# 5250_converter.net
KiCad netlist of a schematic drawn in EAGLE
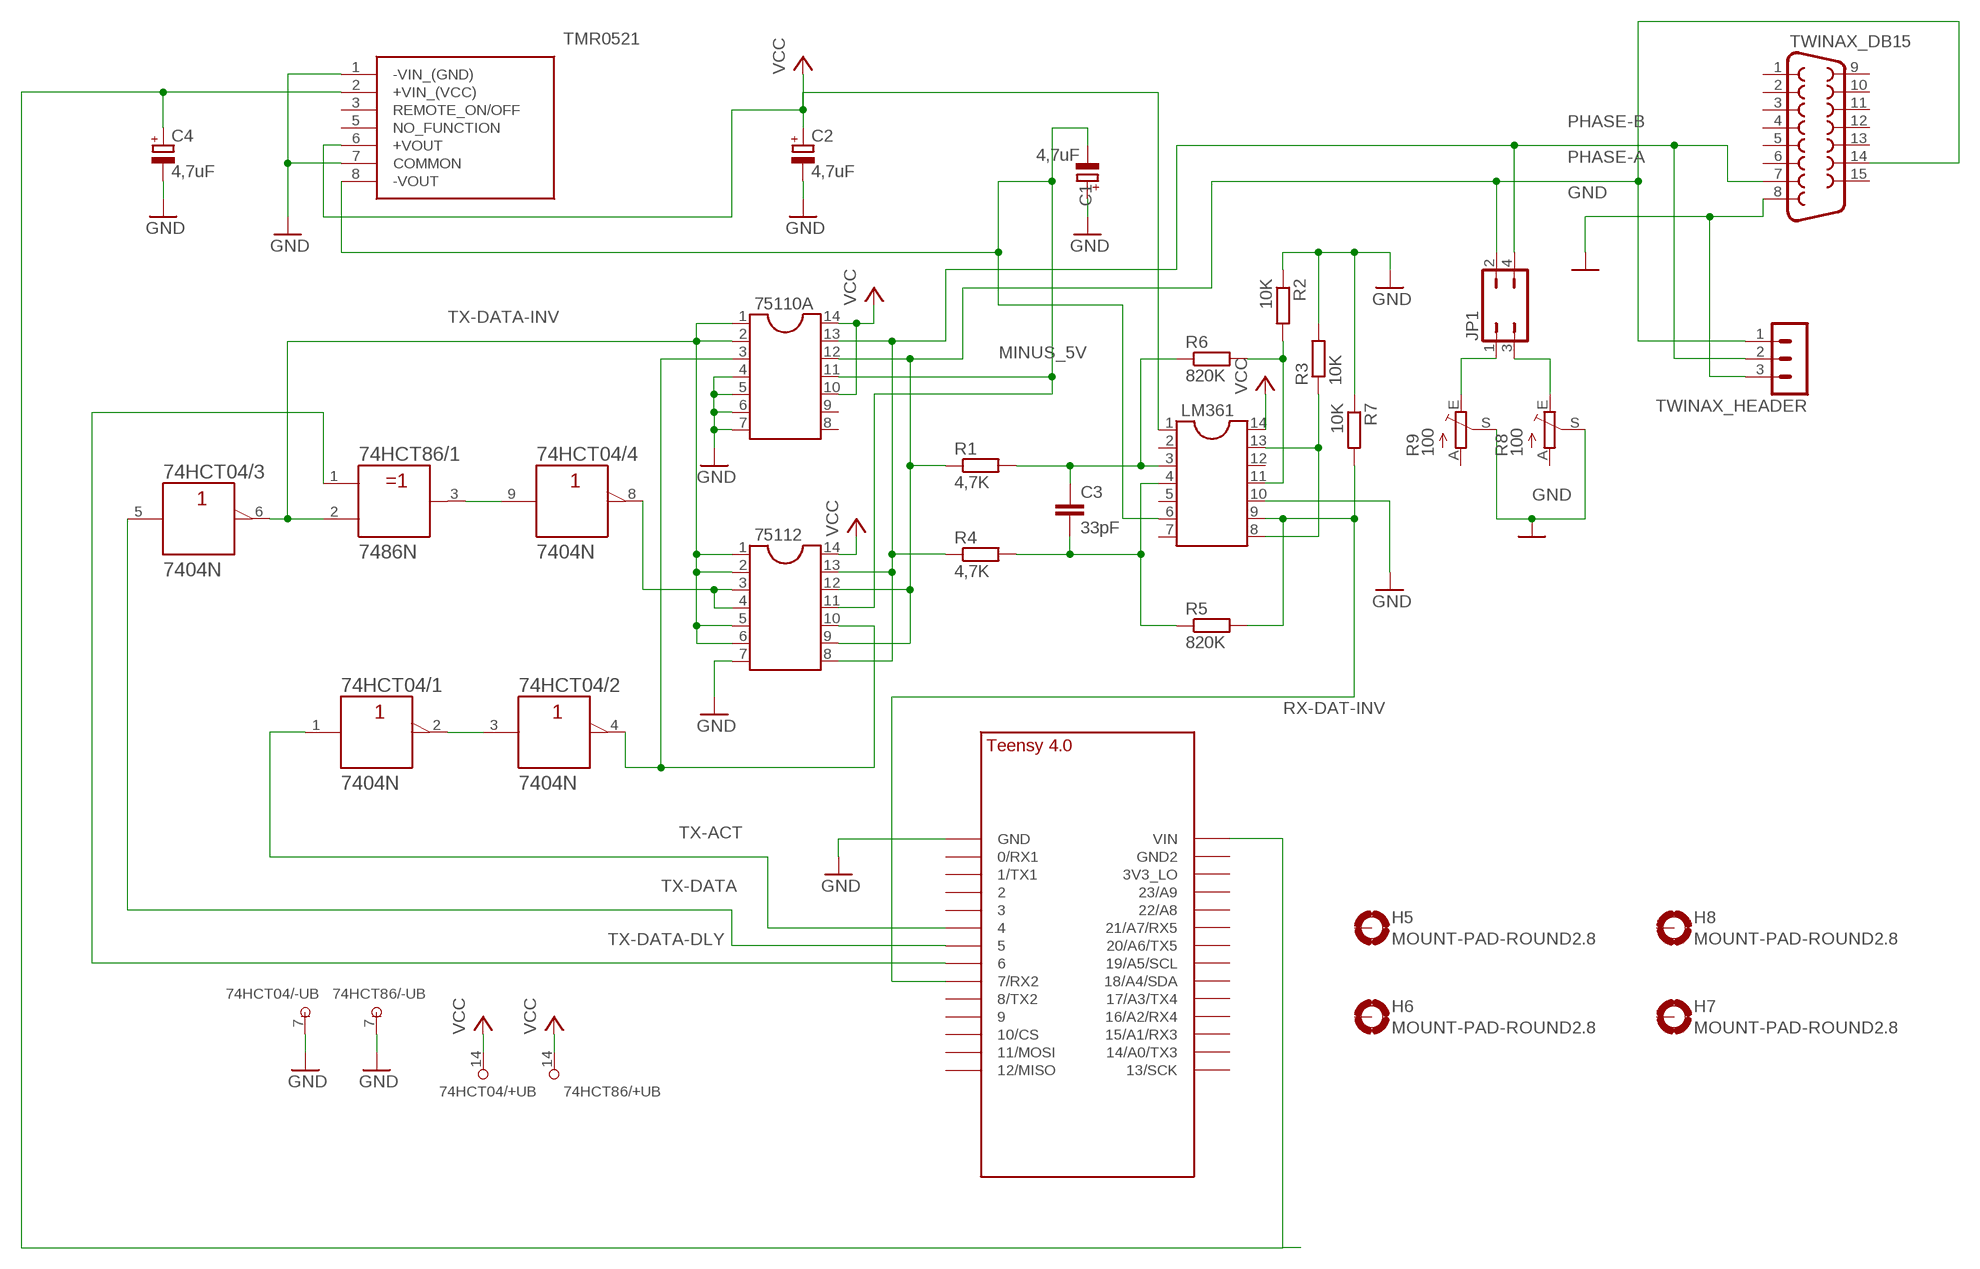
[diagram p0: schematic, sheet 1]

(export (version "E")
  (design (tool "Eeschema 10.0.6"))
  (components
    (comp (ref "74HCT04")
      (value "7404N")
      (footprint "eagle-import:DIL14")
      (libsource (lib "eagle-import") (part "7404N"))
    )
    (comp (ref "74HCT86")
      (value "7486N")
      (footprint "eagle-import:DIL14")
      (libsource (lib "eagle-import") (part "7486N"))
    )
    (comp (ref "75110A")
      (value "DIL14")
      (footprint "eagle-import:DIL14")
      (libsource (lib "eagle-import") (part "DIL14"))
    )
    (comp (ref "75112")
      (value "DIL14")
      (footprint "eagle-import:DIL14")
      (libsource (lib "eagle-import") (part "DIL14"))
    )
    (comp (ref "C1")
      (value "4,7uF")
      (footprint "eagle-import:E2,5-6")
      (libsource (lib "eagle-import") (part "CPOL-EUE2.5-6"))
    )
    (comp (ref "C2")
      (value "4,7uF")
      (footprint "eagle-import:E2,5-6")
      (libsource (lib "eagle-import") (part "CPOL-EUE2.5-6"))
    )
    (comp (ref "C3")
      (value "33pF")
      (footprint "eagle-import:C050-030X075")
      (libsource (lib "eagle-import") (part "C-EU050-030X075"))
    )
    (comp (ref "C4")
      (value "4,7uF")
      (footprint "eagle-import:E2,5-6")
      (libsource (lib "eagle-import") (part "CPOL-EUE2.5-6"))
    )
    (comp (ref "H5")
      (value "MOUNT-PAD-ROUND2.8")
      (footprint "eagle-import:2,8-PAD")
      (libsource (lib "eagle-import") (part "MOUNT-PAD-ROUND2.8"))
    )
    (comp (ref "H6")
      (value "MOUNT-PAD-ROUND2.8")
      (footprint "eagle-import:2,8-PAD")
      (libsource (lib "eagle-import") (part "MOUNT-PAD-ROUND2.8"))
    )
    (comp (ref "H7")
      (value "MOUNT-PAD-ROUND2.8")
      (footprint "eagle-import:2,8-PAD")
      (libsource (lib "eagle-import") (part "MOUNT-PAD-ROUND2.8"))
    )
    (comp (ref "H8")
      (value "MOUNT-PAD-ROUND2.8")
      (footprint "eagle-import:2,8-PAD")
      (libsource (lib "eagle-import") (part "MOUNT-PAD-ROUND2.8"))
    )
    (comp (ref "JP1")
      (value "JP2Q")
      (footprint "eagle-import:JP2Q")
      (libsource (lib "eagle-import") (part "JP2Q"))
    )
    (comp (ref "LM361")
      (value "DIL14")
      (footprint "eagle-import:DIL14")
      (libsource (lib "eagle-import") (part "DIL14"))
    )
    (comp (ref "R1")
      (value "4,7K")
      (footprint "eagle-import:0207_10")
      (libsource (lib "eagle-import") (part "R-EU_0207/10"))
    )
    (comp (ref "R2")
      (value "10K")
      (footprint "eagle-import:0207_10")
      (libsource (lib "eagle-import") (part "R-EU_0207/10"))
    )
    (comp (ref "R3")
      (value "10K")
      (footprint "eagle-import:0207_10")
      (libsource (lib "eagle-import") (part "R-EU_0207/10"))
    )
    (comp (ref "R4")
      (value "4,7K")
      (footprint "eagle-import:0207_10")
      (libsource (lib "eagle-import") (part "R-EU_0207/10"))
    )
    (comp (ref "R5")
      (value "820K")
      (footprint "eagle-import:0207_10")
      (libsource (lib "eagle-import") (part "R-EU_0207/10"))
    )
    (comp (ref "R6")
      (value "820K")
      (footprint "eagle-import:0207_10")
      (libsource (lib "eagle-import") (part "R-EU_0207/10"))
    )
    (comp (ref "R7")
      (value "10K")
      (footprint "eagle-import:0207_10")
      (libsource (lib "eagle-import") (part "R-EU_0207/10"))
    )
    (comp (ref "R8")
      (value "100")
      (footprint "eagle-import:CA9V")
      (libsource (lib "eagle-import") (part "TRIM_EU-CA9V"))
    )
    (comp (ref "R9")
      (value "100")
      (footprint "eagle-import:CA9V")
      (libsource (lib "eagle-import") (part "TRIM_EU-CA9V"))
    )
    (comp (ref "TMR0521")
      (value "TMR0521")
      (footprint "eagle-import:TMR0521")
      (fields
        (field (name "MANUFACTURER_PART_NUMBER") "TMR 3-2422")
        (field (name "MOUSER_PART_NUMBER") "495-TMR-3-2422")
        (field (name "RS_PART_NUMBER") "0438082")
      )
      (libsource (lib "eagle-import") (part "TMR0521TMR0521"))
    )
    (comp (ref "TWINAX_DB15")
      (value "F15H")
      (footprint "eagle-import:F15H")
      (libsource (lib "eagle-import") (part "F15H"))
    )
    (comp (ref "TWINAX_HEADER")
      (value "MA03-1")
      (footprint "eagle-import:MA03-1")
      (libsource (lib "eagle-import") (part "MA03-1"))
    )
    (comp (ref "U$1")
      (value "TEENSY_4.0-BASIC")
      (footprint "eagle-import:TEENSY_4.0-BASIC")
      (libsource (lib "eagle-import") (part "TEENSY_4.0-BASIC"))
    )
  )
  (nets
    (net (code "1") (name "/MINUS_5V") (class "Default")
      (node (ref "75110A") (pin "11") (pinfunction "11_11") (pintype "passive"))
      (node (ref "75112") (pin "11") (pinfunction "11_11") (pintype "passive"))
      (node (ref "C1") (pin "-") (pinfunction "-_-") (pintype "passive"))
      (node (ref "LM361") (pin "6") (pinfunction "6_6") (pintype "passive"))
      (node (ref "TMR0521") (pin "8") (pinfunction "-VOUT_8") (pintype "bidirectional"))
    )
    (net (code "2") (name "/PHASE-A") (class "Default")
      (node (ref "75110A") (pin "12") (pinfunction "12_12") (pintype "passive"))
      (node (ref "75112") (pin "12") (pinfunction "12_12") (pintype "passive"))
      (node (ref "75112") (pin "9") (pinfunction "9_9") (pintype "passive"))
      (node (ref "JP1") (pin "2") (pinfunction "2_2") (pintype "passive"))
      (node (ref "R1") (pin "1") (pinfunction "1_1") (pintype "passive"))
      (node (ref "TWINAX_DB15") (pin "14") (pinfunction "14_14") (pintype "passive"))
      (node (ref "TWINAX_HEADER") (pin "1") (pinfunction "1_1") (pintype "passive"))
    )
    (net (code "3") (name "/PHASE-B") (class "Default")
      (node (ref "75110A") (pin "13") (pinfunction "13_13") (pintype "passive"))
      (node (ref "75112") (pin "13") (pinfunction "13_13") (pintype "passive"))
      (node (ref "75112") (pin "8") (pinfunction "8_8") (pintype "passive"))
      (node (ref "JP1") (pin "4") (pinfunction "4_4") (pintype "passive"))
      (node (ref "R4") (pin "1") (pinfunction "1_1") (pintype "passive"))
      (node (ref "TWINAX_DB15") (pin "7") (pinfunction "7_7") (pintype "passive"))
      (node (ref "TWINAX_HEADER") (pin "2") (pinfunction "2_2") (pintype "passive"))
    )
    (net (code "4") (name "/RX-DAT-INV") (class "Default")
      (node (ref "LM361") (pin "9") (pinfunction "9_9") (pintype "passive"))
      (node (ref "R5") (pin "2") (pinfunction "2_2") (pintype "passive"))
      (node (ref "R7") (pin "2") (pinfunction "2_2") (pintype "passive"))
      (node (ref "U$1") (pin "7") (pinfunction "7/RX2_7") (pintype "bidirectional"))
    )
    (net (code "5") (name "/TX-ACT") (class "Default")
      (node (ref "74HCT04") (pin "1") (pinfunction "A_1") (pintype "input"))
      (node (ref "U$1") (pin "4/CANRX") (pinfunction "4_4/CANRX") (pintype "bidirectional"))
    )
    (net (code "6") (name "/TX-DATA") (class "Default")
      (node (ref "74HCT04") (pin "5") (pinfunction "A_5") (pintype "input"))
      (node (ref "U$1") (pin "5") (pinfunction "5_5") (pintype "bidirectional"))
    )
    (net (code "7") (name "/TX-DATA-DLY") (class "Default")
      (node (ref "74HCT86") (pin "1") (pinfunction "A_1") (pintype "input"))
      (node (ref "U$1") (pin "6") (pinfunction "6_6") (pintype "bidirectional"))
    )
    (net (code "8") (name "/TX-DATA-INV") (class "Default")
      (node (ref "74HCT04") (pin "6") (pinfunction "Y_6") (pintype "output"))
      (node (ref "74HCT86") (pin "2") (pinfunction "B_2") (pintype "input"))
      (node (ref "75110A") (pin "1") (pinfunction "1_1") (pintype "passive"))
      (node (ref "75110A") (pin "2") (pinfunction "2_2") (pintype "passive"))
      (node (ref "75112") (pin "1") (pinfunction "1_1") (pintype "passive"))
      (node (ref "75112") (pin "2") (pinfunction "2_2") (pintype "passive"))
      (node (ref "75112") (pin "5") (pinfunction "5_5") (pintype "passive"))
      (node (ref "75112") (pin "6") (pinfunction "6_6") (pintype "passive"))
    )
    (net (code "9") (name "GND") (class "Default")
      (node (ref "74HCT04") (pin "7") (pinfunction "-UB_7") (pintype "power_in"))
      (node (ref "74HCT86") (pin "7") (pinfunction "-UB_7") (pintype "power_in"))
      (node (ref "75110A") (pin "4") (pinfunction "4_4") (pintype "passive"))
      (node (ref "75110A") (pin "5") (pinfunction "5_5") (pintype "passive"))
      (node (ref "75110A") (pin "6") (pinfunction "6_6") (pintype "passive"))
      (node (ref "75110A") (pin "7") (pinfunction "7_7") (pintype "passive"))
      (node (ref "75112") (pin "7") (pinfunction "7_7") (pintype "passive"))
      (node (ref "C1") (pin "+") (pinfunction "+_+") (pintype "passive"))
      (node (ref "C2") (pin "-") (pinfunction "-_-") (pintype "passive"))
      (node (ref "C4") (pin "-") (pinfunction "-_-") (pintype "passive"))
      (node (ref "LM361") (pin "10") (pinfunction "10_10") (pintype "passive"))
      (node (ref "R2") (pin "1") (pinfunction "1_1") (pintype "passive"))
      (node (ref "R3") (pin "2") (pinfunction "2_2") (pintype "passive"))
      (node (ref "R7") (pin "1") (pinfunction "1_1") (pintype "passive"))
      (node (ref "R8") (pin "S") (pinfunction "S_S") (pintype "passive"))
      (node (ref "R9") (pin "S") (pinfunction "S_S") (pintype "passive"))
      (node (ref "TMR0521") (pin "1") (pinfunction "-VIN_(GND)_1") (pintype "bidirectional"))
      (node (ref "TMR0521") (pin "7") (pinfunction "COMMON_7") (pintype "bidirectional"))
      (node (ref "TWINAX_DB15") (pin "8") (pinfunction "8_8") (pintype "passive"))
      (node (ref "TWINAX_HEADER") (pin "3") (pinfunction "3_3") (pintype "passive"))
      (node (ref "U$1") (pin "GND") (pinfunction "GND_GND") (pintype "bidirectional"))
    )
    (net (code "10") (name "Net-(74HCT04C-Y)") (class "Default")
      (node (ref "74HCT04") (pin "2") (pinfunction "Y_2") (pintype "output"))
      (node (ref "74HCT04") (pin "3") (pinfunction "A_3") (pintype "input"))
    )
    (net (code "11") (name "Net-(74HCT04D-Y)") (class "Default")
      (node (ref "74HCT04") (pin "4") (pinfunction "Y_4") (pintype "output"))
      (node (ref "75110A") (pin "3") (pinfunction "3_3") (pintype "passive"))
      (node (ref "75112") (pin "10") (pinfunction "10_10") (pintype "passive"))
    )
    (net (code "12") (name "Net-(74HCT04F-A)") (class "Default")
      (node (ref "74HCT04") (pin "9") (pinfunction "A_9") (pintype "input"))
      (node (ref "74HCT86") (pin "3") (pinfunction "Y_3") (pintype "output"))
    )
    (net (code "13") (name "Net-(74HCT04F-Y)") (class "Default")
      (node (ref "74HCT04") (pin "8") (pinfunction "Y_8") (pintype "output"))
      (node (ref "75112") (pin "3") (pinfunction "3_3") (pintype "passive"))
      (node (ref "75112") (pin "4") (pinfunction "4_4") (pintype "passive"))
    )
    (net (code "14") (name "Net-(C3-Pad1)") (class "Default")
      (node (ref "C3") (pin "1") (pinfunction "1_1") (pintype "passive"))
      (node (ref "LM361") (pin "3") (pinfunction "3_3") (pintype "passive"))
      (node (ref "R1") (pin "2") (pinfunction "2_2") (pintype "passive"))
      (node (ref "R6") (pin "1") (pinfunction "1_1") (pintype "passive"))
    )
    (net (code "15") (name "Net-(C3-Pad2)") (class "Default")
      (node (ref "C3") (pin "2") (pinfunction "2_2") (pintype "passive"))
      (node (ref "LM361") (pin "4") (pinfunction "4_4") (pintype "passive"))
      (node (ref "R4") (pin "2") (pinfunction "2_2") (pintype "passive"))
      (node (ref "R5") (pin "1") (pinfunction "1_1") (pintype "passive"))
    )
    (net (code "16") (name "Net-(JP1-Pad1)") (class "Default")
      (node (ref "JP1") (pin "1") (pinfunction "1_1") (pintype "passive"))
      (node (ref "R9") (pin "E") (pinfunction "E_E") (pintype "passive"))
    )
    (net (code "17") (name "Net-(JP1-Pad3)") (class "Default")
      (node (ref "JP1") (pin "3") (pinfunction "3_3") (pintype "passive"))
      (node (ref "R8") (pin "E") (pinfunction "E_E") (pintype "passive"))
    )
    (net (code "18") (name "Net-(LM361-Pad11)") (class "Default")
      (node (ref "LM361") (pin "11") (pinfunction "11_11") (pintype "passive"))
      (node (ref "R2") (pin "2") (pinfunction "2_2") (pintype "passive"))
      (node (ref "R6") (pin "2") (pinfunction "2_2") (pintype "passive"))
    )
    (net (code "19") (name "Net-(LM361-Pad13)") (class "Default")
      (node (ref "LM361") (pin "13") (pinfunction "13_13") (pintype "passive"))
      (node (ref "LM361") (pin "8") (pinfunction "8_8") (pintype "passive"))
      (node (ref "R3") (pin "1") (pinfunction "1_1") (pintype "passive"))
    )
    (net (code "20") (name "Net-(TMR0521-+VIN_(VCC))") (class "Default")
      (node (ref "C4") (pin "+") (pinfunction "+_+") (pintype "passive"))
      (node (ref "TMR0521") (pin "2") (pinfunction "+VIN_(VCC)_2") (pintype "bidirectional"))
      (node (ref "U$1") (pin "VIN") (pinfunction "VIN_VIN") (pintype "bidirectional"))
    )
    (net (code "21") (name "VCC") (class "Default")
      (node (ref "74HCT04") (pin "14") (pinfunction "+UB_14") (pintype "power_in"))
      (node (ref "74HCT86") (pin "14") (pinfunction "+UB_14") (pintype "power_in"))
      (node (ref "75110A") (pin "10") (pinfunction "10_10") (pintype "passive"))
      (node (ref "75110A") (pin "14") (pinfunction "14_14") (pintype "passive"))
      (node (ref "75112") (pin "14") (pinfunction "14_14") (pintype "passive"))
      (node (ref "C2") (pin "+") (pinfunction "+_+") (pintype "passive"))
      (node (ref "LM361") (pin "1") (pinfunction "1_1") (pintype "passive"))
      (node (ref "LM361") (pin "14") (pinfunction "14_14") (pintype "passive"))
      (node (ref "TMR0521") (pin "6") (pinfunction "+VOUT_6") (pintype "bidirectional"))
    )
    (net (code "22") (name "unconnected-(75110A-Pad8)") (class "Default")
      (node (ref "75110A") (pin "8") (pinfunction "8_8") (pintype "passive"))
    )
    (net (code "23") (name "unconnected-(75110A-Pad9)") (class "Default")
      (node (ref "75110A") (pin "9") (pinfunction "9_9") (pintype "passive"))
    )
    (net (code "24") (name "unconnected-(H5-MOUNT-PadB2,8)") (class "Default")
      (node (ref "H5") (pin "B2,8") (pinfunction "MOUNT_B2,8") (pintype "passive"))
    )
    (net (code "25") (name "unconnected-(H6-MOUNT-PadB2,8)") (class "Default")
      (node (ref "H6") (pin "B2,8") (pinfunction "MOUNT_B2,8") (pintype "passive"))
    )
    (net (code "26") (name "unconnected-(H7-MOUNT-PadB2,8)") (class "Default")
      (node (ref "H7") (pin "B2,8") (pinfunction "MOUNT_B2,8") (pintype "passive"))
    )
    (net (code "27") (name "unconnected-(H8-MOUNT-PadB2,8)") (class "Default")
      (node (ref "H8") (pin "B2,8") (pinfunction "MOUNT_B2,8") (pintype "passive"))
    )
    (net (code "28") (name "unconnected-(LM361-Pad2)") (class "Default")
      (node (ref "LM361") (pin "2") (pinfunction "2_2") (pintype "passive"))
    )
    (net (code "29") (name "unconnected-(LM361-Pad5)") (class "Default")
      (node (ref "LM361") (pin "5") (pinfunction "5_5") (pintype "passive"))
    )
    (net (code "30") (name "unconnected-(LM361-Pad7)") (class "Default")
      (node (ref "LM361") (pin "7") (pinfunction "7_7") (pintype "passive"))
    )
    (net (code "31") (name "unconnected-(LM361-Pad12)") (class "Default")
      (node (ref "LM361") (pin "12") (pinfunction "12_12") (pintype "passive"))
    )
    (net (code "32") (name "unconnected-(R8-PadA)") (class "Default")
      (node (ref "R8") (pin "A") (pinfunction "A_A") (pintype "passive"))
    )
    (net (code "33") (name "unconnected-(R9-PadA)") (class "Default")
      (node (ref "R9") (pin "A") (pinfunction "A_A") (pintype "passive"))
    )
    (net (code "34") (name "unconnected-(TMR0521-NO_FUNCTION-Pad5)") (class "Default")
      (node (ref "TMR0521") (pin "5") (pinfunction "NO_FUNCTION_5") (pintype "bidirectional"))
    )
    (net (code "35") (name "unconnected-(TMR0521-REMOTE_ON{slash}OFF-Pad3)") (class "Default")
      (node (ref "TMR0521") (pin "3") (pinfunction "REMOTE_ON/OFF_3") (pintype "bidirectional"))
    )
    (net (code "36") (name "unconnected-(TWINAX_DB15-Pad1)") (class "Default")
      (node (ref "TWINAX_DB15") (pin "1") (pinfunction "1_1") (pintype "passive"))
    )
    (net (code "37") (name "unconnected-(TWINAX_DB15-Pad2)") (class "Default")
      (node (ref "TWINAX_DB15") (pin "2") (pinfunction "2_2") (pintype "passive"))
    )
    (net (code "38") (name "unconnected-(TWINAX_DB15-Pad3)") (class "Default")
      (node (ref "TWINAX_DB15") (pin "3") (pinfunction "3_3") (pintype "passive"))
    )
    (net (code "39") (name "unconnected-(TWINAX_DB15-Pad4)") (class "Default")
      (node (ref "TWINAX_DB15") (pin "4") (pinfunction "4_4") (pintype "passive"))
    )
    (net (code "40") (name "unconnected-(TWINAX_DB15-Pad5)") (class "Default")
      (node (ref "TWINAX_DB15") (pin "5") (pinfunction "5_5") (pintype "passive"))
    )
    (net (code "41") (name "unconnected-(TWINAX_DB15-Pad6)") (class "Default")
      (node (ref "TWINAX_DB15") (pin "6") (pinfunction "6_6") (pintype "passive"))
    )
    (net (code "42") (name "unconnected-(TWINAX_DB15-Pad9)") (class "Default")
      (node (ref "TWINAX_DB15") (pin "9") (pinfunction "9_9") (pintype "passive"))
    )
    (net (code "43") (name "unconnected-(TWINAX_DB15-Pad10)") (class "Default")
      (node (ref "TWINAX_DB15") (pin "10") (pinfunction "10_10") (pintype "passive"))
    )
    (net (code "44") (name "unconnected-(TWINAX_DB15-Pad11)") (class "Default")
      (node (ref "TWINAX_DB15") (pin "11") (pinfunction "11_11") (pintype "passive"))
    )
    (net (code "45") (name "unconnected-(TWINAX_DB15-Pad12)") (class "Default")
      (node (ref "TWINAX_DB15") (pin "12") (pinfunction "12_12") (pintype "passive"))
    )
    (net (code "46") (name "unconnected-(TWINAX_DB15-Pad13)") (class "Default")
      (node (ref "TWINAX_DB15") (pin "13") (pinfunction "13_13") (pintype "passive"))
    )
    (net (code "47") (name "unconnected-(TWINAX_DB15-Pad15)") (class "Default")
      (node (ref "TWINAX_DB15") (pin "15") (pinfunction "15_15") (pintype "passive"))
    )
    (net (code "48") (name "unconnected-(U$1-0{slash}RX1-Pad0{slash}RX)") (class "Default")
      (node (ref "U$1") (pin "0/RX") (pinfunction "0/RX1_0/RX") (pintype "bidirectional"))
    )
    (net (code "49") (name "unconnected-(U$1-1{slash}TX1-Pad1{slash}TX)") (class "Default")
      (node (ref "U$1") (pin "1/TX") (pinfunction "1/TX1_1/TX") (pintype "bidirectional"))
    )
    (net (code "50") (name "unconnected-(U$1-3-Pad3{slash}CANTX)") (class "Default")
      (node (ref "U$1") (pin "3/CANTX") (pinfunction "3_3/CANTX") (pintype "bidirectional"))
    )
    (net (code "51") (name "unconnected-(U$1-8{slash}TX2-Pad8)") (class "Default")
      (node (ref "U$1") (pin "8") (pinfunction "8/TX2_8") (pintype "bidirectional"))
    )
    (net (code "52") (name "unconnected-(U$1-9-Pad9{slash}CS)") (class "Default")
      (node (ref "U$1") (pin "9/CS") (pinfunction "9_9/CS") (pintype "bidirectional"))
    )
    (net (code "53") (name "unconnected-(U$1-14{slash}A0{slash}TX3-Pad14{slash}A0)") (class "Default")
      (node (ref "U$1") (pin "14/A0") (pinfunction "14/A0/TX3_14/A0") (pintype "bidirectional"))
    )
    (net (code "54") (name "unconnected-(U$1-15{slash}A1{slash}RX3-Pad15{slash}A1)") (class "Default")
      (node (ref "U$1") (pin "15/A1") (pinfunction "15/A1/RX3_15/A1") (pintype "bidirectional"))
    )
    (net (code "55") (name "unconnected-(U$1-16{slash}A2{slash}RX4-Pad16{slash}A2)") (class "Default")
      (node (ref "U$1") (pin "16/A2") (pinfunction "16/A2/RX4_16/A2") (pintype "bidirectional"))
    )
    (net (code "56") (name "unconnected-(U$1-17{slash}A3{slash}TX4-Pad17{slash}A3)") (class "Default")
      (node (ref "U$1") (pin "17/A3") (pinfunction "17/A3/TX4_17/A3") (pintype "bidirectional"))
    )
    (net (code "57") (name "unconnected-(U$1-20{slash}A6{slash}TX5-Pad20{slash}A6)") (class "Default")
      (node (ref "U$1") (pin "20/A6") (pinfunction "20/A6/TX5_20/A6") (pintype "bidirectional"))
    )
    (net (code "58") (name "unconnected-(U$1-21{slash}A7{slash}RX5-Pad21{slash}A7)") (class "Default")
      (node (ref "U$1") (pin "21/A7") (pinfunction "21/A7/RX5_21/A7") (pintype "bidirectional"))
    )
    (net (code "59") (name "unconnected-(U$1-Pad2)") (class "Default")
      (node (ref "U$1") (pin "2") (pinfunction "2_2") (pintype "bidirectional"))
    )
    (net (code "60") (name "unconnected-(U$1-Pad3V3_LO)") (class "Default")
      (node (ref "U$1") (pin "3V3_LO") (pinfunction "3V3_LO_3V3_LO") (pintype "bidirectional"))
    )
    (net (code "61") (name "unconnected-(U$1-Pad10{slash}CS)") (class "Default")
      (node (ref "U$1") (pin "10/CS") (pinfunction "10/CS_10/CS") (pintype "bidirectional"))
    )
    (net (code "62") (name "unconnected-(U$1-Pad11{slash}MOSI)") (class "Default")
      (node (ref "U$1") (pin "11/MOSI") (pinfunction "11/MOSI_11/MOSI") (pintype "bidirectional"))
    )
    (net (code "63") (name "unconnected-(U$1-Pad12{slash}MISO)") (class "Default")
      (node (ref "U$1") (pin "12/MISO") (pinfunction "12/MISO_12/MISO") (pintype "bidirectional"))
    )
    (net (code "64") (name "unconnected-(U$1-Pad13{slash}SCK)") (class "Default")
      (node (ref "U$1") (pin "13/SCK") (pinfunction "13/SCK_13/SCK") (pintype "bidirectional"))
    )
    (net (code "65") (name "unconnected-(U$1-Pad18{slash}A4{slash}SDA)") (class "Default")
      (node (ref "U$1") (pin "18/A4/SDA") (pinfunction "18/A4/SDA_18/A4/SDA") (pintype "bidirectional"))
    )
    (net (code "66") (name "unconnected-(U$1-Pad19{slash}A5{slash}SCL)") (class "Default")
      (node (ref "U$1") (pin "19/A5/SCL") (pinfunction "19/A5/SCL_19/A5/SCL") (pintype "bidirectional"))
    )
    (net (code "67") (name "unconnected-(U$1-Pad22{slash}A8)") (class "Default")
      (node (ref "U$1") (pin "22/A8") (pinfunction "22/A8_22/A8") (pintype "bidirectional"))
    )
    (net (code "68") (name "unconnected-(U$1-Pad23{slash}A9)") (class "Default")
      (node (ref "U$1") (pin "23/A9") (pinfunction "23/A9_23/A9") (pintype "bidirectional"))
    )
    (net (code "69") (name "unconnected-(U$1-PadGND2)") (class "Default")
      (node (ref "U$1") (pin "GND2") (pinfunction "GND2_GND2") (pintype "bidirectional"))
    )
  )
)
